# sensors.net
KiCad netlist of a schematic drawn in Altium Designer
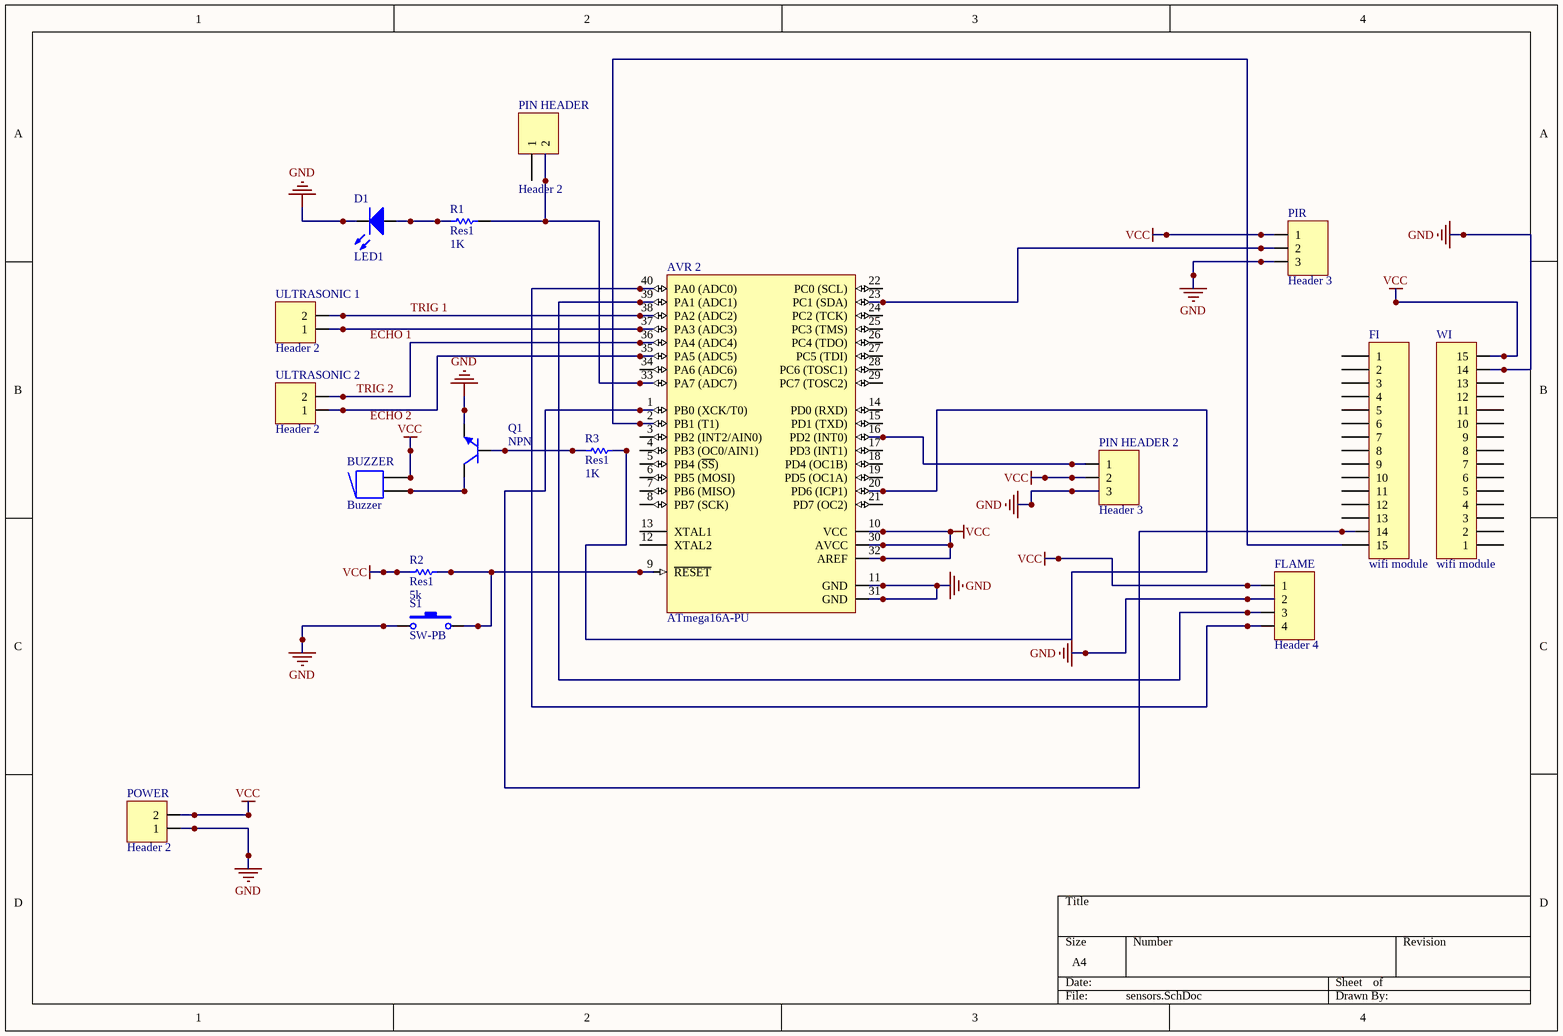
[diagram p0: sensors.SchDoc]

(export (version "E")
  (design (tool "Eeschema 10.0.6"))
  (components
    (comp (ref "AVR 2")
      (value "ATmega16A-PU")
      (footprint "40P6")
      (fields (field (name "PUBLISHER") "Altium Limited"))
      (libsource (lib "Atmel Microcontroller 8-Bit megaAVR") (part "ATmega16A-PU"))
    )
    (comp (ref "BUZZER")
      (value "Buzzer")
      (footprint "ABSM-1574")
      (description "Magnetic Transducer Buzzer")
      (fields (field (name "PUBLISHER") "Altium Limited"))
      (libsource (lib "Miscellaneous Devices") (part "Buzzer"))
    )
    (comp (ref "D1")
      (value "LED1")
      (footprint "LED-1")
      (description "Typical RED GaAs LED")
      (fields (field (name "PUBLISHER") "Altium Limited"))
      (libsource (lib "Miscellaneous Devices") (part "LED1"))
    )
    (comp (ref "FI")
      (value "wifi module")
      (footprint "HDR1X15")
      (description "Header, 15-Pin")
      (fields (field (name "PUBLISHER") "Altium Limited"))
      (libsource (lib "") (part "Header 15_1"))
    )
    (comp (ref "FLAME")
      (value "Header 4")
      (footprint "HDR1X4")
      (description "Header, 4-Pin")
      (fields (field (name "PUBLISHER") "Altium Limited"))
      (libsource (lib "Miscellaneous Connectors") (part "Header 4"))
    )
    (comp (ref "PIN HEADER")
      (value "Header 2")
      (footprint "HDR1X2")
      (description "Header, 2-Pin")
      (fields (field (name "PUBLISHER") "Altium Limited"))
      (libsource (lib "") (part "Header 2_1"))
    )
    (comp (ref "PIN HEADER 2")
      (value "Header 3")
      (footprint "HDR1X3")
      (description "Header, 3-Pin")
      (fields (field (name "PUBLISHER") "Altium Limited"))
      (libsource (lib "Miscellaneous Connectors") (part "Header 3"))
    )
    (comp (ref "PIR")
      (value "Header 3")
      (footprint "HDR1X3")
      (description "Header, 3-Pin")
      (fields (field (name "PUBLISHER") "Altium Limited"))
      (libsource (lib "Miscellaneous Connectors") (part "Header 3"))
    )
    (comp (ref "POWER")
      (value "Header 2")
      (footprint "HDR1X2")
      (description "Header, 2-Pin")
      (fields (field (name "PUBLISHER") "Altium Limited"))
      (libsource (lib "Miscellaneous Connectors") (part "Header 2"))
    )
    (comp (ref "Q1")
      (value "NPN")
      (footprint "TO-226-AA")
      (description "NPN Bipolar Transistor")
      (fields (field (name "PUBLISHER") "Altium Limited"))
      (libsource (lib "Miscellaneous Devices") (part "NPN"))
    )
    (comp (ref "R1")
      (value "Res1")
      (footprint "AXIAL-0.3")
      (description "Resistor")
      (fields (field (name "ALTIUM_VALUE") "1K") (field (name "PUBLISHER") "Altium Limited"))
      (libsource (lib "Miscellaneous Devices") (part "Res1"))
    )
    (comp (ref "R2")
      (value "Res1")
      (footprint "AXIAL-0.3")
      (description "Resistor")
      (fields (field (name "ALTIUM_VALUE") "5k") (field (name "PUBLISHER") "Altium Limited"))
      (libsource (lib "Miscellaneous Devices") (part "Res1"))
    )
    (comp (ref "R3")
      (value "Res1")
      (footprint "AXIAL-0.3")
      (description "Resistor")
      (fields (field (name "ALTIUM_VALUE") "1K") (field (name "PUBLISHER") "Altium Limited"))
      (libsource (lib "Miscellaneous Devices") (part "Res1"))
    )
    (comp (ref "S1")
      (value "SW-PB")
      (footprint "SPST-2")
      (description "Switch")
      (fields (field (name "PUBLISHER") "Altium Limited"))
      (libsource (lib "Miscellaneous Devices") (part "SW-PB"))
    )
    (comp (ref "ULTRASONIC 1")
      (value "Header 2")
      (footprint "HDR1X2")
      (description "Header, 2-Pin")
      (fields (field (name "PUBLISHER") "Altium Limited"))
      (libsource (lib "Miscellaneous Connectors") (part "Header 2"))
    )
    (comp (ref "ULTRASONIC 2")
      (value "Header 2")
      (footprint "HDR1X2")
      (description "Header, 2-Pin")
      (fields (field (name "PUBLISHER") "Altium Limited"))
      (libsource (lib "Miscellaneous Connectors") (part "Header 2"))
    )
    (comp (ref "WI")
      (value "wifi module")
      (footprint "HDR1X15")
      (description "Header, 15-Pin")
      (fields (field (name "PUBLISHER") "Altium Limited"))
      (libsource (lib "Miscellaneous Connectors") (part "Header 15"))
    )
  )
  (nets
    (net (code "3") (name "/TRIG 1") (class "Default")
      (node (ref "AVR 2") (pin "38") (pinfunction "PA2_(ADC2)_38") (pintype "bidirectional"))
      (node (ref "ULTRASONIC 1") (pin "2") (pinfunction "2_2") (pintype "passive"))
    )
    (net (code "4") (name "/TRIG 2") (class "Default")
      (node (ref "AVR 2") (pin "36") (pinfunction "PA4_(ADC4)_36") (pintype "bidirectional"))
      (node (ref "ULTRASONIC 2") (pin "2") (pinfunction "2_2") (pintype "passive"))
    )
    (net (code "5") (name "GND") (class "Default")
      (node (ref "AVR 2") (pin "11") (pinfunction "GND_11") (pintype "power_in"))
      (node (ref "AVR 2") (pin "31") (pinfunction "GND_31") (pintype "power_in"))
      (node (ref "D1") (pin "2") (pinfunction "K_2") (pintype "passive"))
      (node (ref "FLAME") (pin "2") (pinfunction "2_2") (pintype "passive"))
      (node (ref "PIN HEADER 2") (pin "3") (pinfunction "3_3") (pintype "passive"))
      (node (ref "PIR") (pin "3") (pinfunction "3_3") (pintype "passive"))
      (node (ref "POWER") (pin "1") (pinfunction "1_1") (pintype "passive"))
      (node (ref "Q1") (pin "3") (pinfunction "E_3") (pintype "passive"))
      (node (ref "S1") (pin "1") (pinfunction "1_1") (pintype "passive"))
      (node (ref "WI") (pin "14") (pinfunction "14_14") (pintype "passive"))
    )
    (net (code "6") (name "Net-(AVR 2-PA0_(ADC0))") (class "Default")
      (node (ref "AVR 2") (pin "40") (pinfunction "PA0_(ADC0)_40") (pintype "bidirectional"))
      (node (ref "FLAME") (pin "4") (pinfunction "4_4") (pintype "passive"))
    )
    (net (code "7") (name "Net-(AVR 2-PA1_(ADC1))") (class "Default")
      (node (ref "AVR 2") (pin "39") (pinfunction "PA1_(ADC1)_39") (pintype "bidirectional"))
      (node (ref "FLAME") (pin "3") (pinfunction "3_3") (pintype "passive"))
    )
    (net (code "8") (name "Net-(AVR 2-PA3_(ADC3))") (class "Default")
      (node (ref "AVR 2") (pin "37") (pinfunction "PA3_(ADC3)_37") (pintype "bidirectional"))
      (node (ref "ULTRASONIC 1") (pin "1") (pinfunction "1_1") (pintype "passive"))
    )
    (net (code "9") (name "Net-(AVR 2-PA5_(ADC5))") (class "Default")
      (node (ref "AVR 2") (pin "35") (pinfunction "PA5_(ADC5)_35") (pintype "bidirectional"))
      (node (ref "ULTRASONIC 2") (pin "1") (pinfunction "1_1") (pintype "passive"))
    )
    (net (code "10") (name "Net-(AVR 2-PA7_(ADC7))") (class "Default")
      (node (ref "AVR 2") (pin "33") (pinfunction "PA7_(ADC7)_33") (pintype "bidirectional"))
      (node (ref "PIN HEADER") (pin "2") (pinfunction "2_2") (pintype "passive"))
      (node (ref "R1") (pin "1") (pinfunction "1_1") (pintype "passive"))
    )
    (net (code "11") (name "Net-(AVR 2-PB0_(XCK{slash}T0))") (class "Default")
      (node (ref "AVR 2") (pin "1") (pinfunction "PB0_(XCK/T0)_1") (pintype "bidirectional"))
      (node (ref "FI") (pin "14") (pinfunction "14_14") (pintype "passive"))
    )
    (net (code "12") (name "Net-(AVR 2-PB1_(T1))") (class "Default")
      (node (ref "AVR 2") (pin "2") (pinfunction "PB1_(T1)_2") (pintype "bidirectional"))
      (node (ref "FI") (pin "15") (pinfunction "15_15") (pintype "passive"))
    )
    (net (code "13") (name "Net-(AVR 2-PC1_(SDA))") (class "Default")
      (node (ref "AVR 2") (pin "23") (pinfunction "PC1_(SDA)_23") (pintype "bidirectional"))
      (node (ref "PIR") (pin "2") (pinfunction "2_2") (pintype "passive"))
    )
    (net (code "14") (name "Net-(AVR 2-PD2_(INT0))") (class "Default")
      (node (ref "AVR 2") (pin "16") (pinfunction "PD2_(INT0)_16") (pintype "bidirectional"))
      (node (ref "PIN HEADER 2") (pin "1") (pinfunction "1_1") (pintype "passive"))
    )
    (net (code "15") (name "Net-(AVR 2-PD6_(ICP1))") (class "Default")
      (node (ref "AVR 2") (pin "20") (pinfunction "PD6_(ICP1)_20") (pintype "bidirectional"))
      (node (ref "R3") (pin "2") (pinfunction "2_2") (pintype "passive"))
    )
    (net (code "16") (name "Net-(AVR 2-~{RESET})") (class "Default")
      (node (ref "AVR 2") (pin "9") (pinfunction "~{RESET}_9") (pintype "input"))
      (node (ref "R2") (pin "1") (pinfunction "1_1") (pintype "passive"))
      (node (ref "S1") (pin "2") (pinfunction "2_2") (pintype "passive"))
    )
    (net (code "17") (name "Net-(D1-A)") (class "Default")
      (node (ref "D1") (pin "1") (pinfunction "A_1") (pintype "passive"))
      (node (ref "R1") (pin "2") (pinfunction "2_2") (pintype "passive"))
    )
    (net (code "18") (name "Net-(Q1-B)") (class "Default")
      (node (ref "Q1") (pin "2") (pinfunction "B_2") (pintype "passive"))
      (node (ref "R3") (pin "1") (pinfunction "1_1") (pintype "passive"))
    )
    (net (code "19") (name "Net-(Q1-C)") (class "Default")
      (node (ref "BUZZER") (pin "1") (pinfunction "1_1") (pintype "passive"))
      (node (ref "BUZZER") (pin "1A") (pinfunction "1A_1A") (pintype "passive"))
      (node (ref "Q1") (pin "1") (pinfunction "C_1") (pintype "passive"))
    )
    (net (code "20") (name "VCC") (class "Default")
      (node (ref "AVR 2") (pin "10") (pinfunction "VCC_10") (pintype "power_in"))
      (node (ref "AVR 2") (pin "30") (pinfunction "AVCC_30") (pintype "power_in"))
      (node (ref "AVR 2") (pin "32") (pinfunction "AREF_32") (pintype "power_in"))
      (node (ref "BUZZER") (pin "2") (pinfunction "2_2") (pintype "passive"))
      (node (ref "BUZZER") (pin "2A") (pinfunction "2A_2A") (pintype "passive"))
      (node (ref "FLAME") (pin "1") (pinfunction "1_1") (pintype "passive"))
      (node (ref "PIN HEADER 2") (pin "2") (pinfunction "2_2") (pintype "passive"))
      (node (ref "PIR") (pin "1") (pinfunction "1_1") (pintype "passive"))
      (node (ref "POWER") (pin "2") (pinfunction "2_2") (pintype "passive"))
      (node (ref "R2") (pin "2") (pinfunction "2_2") (pintype "passive"))
      (node (ref "WI") (pin "15") (pinfunction "15_15") (pintype "passive"))
    )
    (net (code "21") (name "unconnected-(AVR 2-PA6_(ADC6)-Pad34)") (class "Default")
      (node (ref "AVR 2") (pin "34") (pinfunction "PA6_(ADC6)_34") (pintype "bidirectional"))
    )
    (net (code "22") (name "unconnected-(AVR 2-PB2_(INT2{slash}AIN0)-Pad3)") (class "Default")
      (node (ref "AVR 2") (pin "3") (pinfunction "PB2_(INT2/AIN0)_3") (pintype "bidirectional"))
    )
    (net (code "23") (name "unconnected-(AVR 2-PB3_(OC0{slash}AIN1)-Pad4)") (class "Default")
      (node (ref "AVR 2") (pin "4") (pinfunction "PB3_(OC0/AIN1)_4") (pintype "bidirectional"))
    )
    (net (code "24") (name "unconnected-(AVR 2-PB4_(~{SS})-Pad5)") (class "Default")
      (node (ref "AVR 2") (pin "5") (pinfunction "PB4_(~{SS})_5") (pintype "bidirectional"))
    )
    (net (code "25") (name "unconnected-(AVR 2-PB5_(MOSI)-Pad6)") (class "Default")
      (node (ref "AVR 2") (pin "6") (pinfunction "PB5_(MOSI)_6") (pintype "bidirectional"))
    )
    (net (code "26") (name "unconnected-(AVR 2-PB6_(MISO)-Pad7)") (class "Default")
      (node (ref "AVR 2") (pin "7") (pinfunction "PB6_(MISO)_7") (pintype "bidirectional"))
    )
    (net (code "27") (name "unconnected-(AVR 2-PB7_(SCK)-Pad8)") (class "Default")
      (node (ref "AVR 2") (pin "8") (pinfunction "PB7_(SCK)_8") (pintype "bidirectional"))
    )
    (net (code "28") (name "unconnected-(AVR 2-PC0_(SCL)-Pad22)") (class "Default")
      (node (ref "AVR 2") (pin "22") (pinfunction "PC0_(SCL)_22") (pintype "bidirectional"))
    )
    (net (code "29") (name "unconnected-(AVR 2-PC2_(TCK)-Pad24)") (class "Default")
      (node (ref "AVR 2") (pin "24") (pinfunction "PC2_(TCK)_24") (pintype "bidirectional"))
    )
    (net (code "30") (name "unconnected-(AVR 2-PC3_(TMS)-Pad25)") (class "Default")
      (node (ref "AVR 2") (pin "25") (pinfunction "PC3_(TMS)_25") (pintype "bidirectional"))
    )
    (net (code "31") (name "unconnected-(AVR 2-PC4_(TDO)-Pad26)") (class "Default")
      (node (ref "AVR 2") (pin "26") (pinfunction "PC4_(TDO)_26") (pintype "bidirectional"))
    )
    (net (code "32") (name "unconnected-(AVR 2-PC5_(TDI)-Pad27)") (class "Default")
      (node (ref "AVR 2") (pin "27") (pinfunction "PC5_(TDI)_27") (pintype "bidirectional"))
    )
    (net (code "33") (name "unconnected-(AVR 2-PC6_(TOSC1)-Pad28)") (class "Default")
      (node (ref "AVR 2") (pin "28") (pinfunction "PC6_(TOSC1)_28") (pintype "bidirectional"))
    )
    (net (code "34") (name "unconnected-(AVR 2-PC7_(TOSC2)-Pad29)") (class "Default")
      (node (ref "AVR 2") (pin "29") (pinfunction "PC7_(TOSC2)_29") (pintype "bidirectional"))
    )
    (net (code "35") (name "unconnected-(AVR 2-PD0_(RXD)-Pad14)") (class "Default")
      (node (ref "AVR 2") (pin "14") (pinfunction "PD0_(RXD)_14") (pintype "bidirectional"))
    )
    (net (code "36") (name "unconnected-(AVR 2-PD1_(TXD)-Pad15)") (class "Default")
      (node (ref "AVR 2") (pin "15") (pinfunction "PD1_(TXD)_15") (pintype "bidirectional"))
    )
    (net (code "37") (name "unconnected-(AVR 2-PD3_(INT1)-Pad17)") (class "Default")
      (node (ref "AVR 2") (pin "17") (pinfunction "PD3_(INT1)_17") (pintype "bidirectional"))
    )
    (net (code "38") (name "unconnected-(AVR 2-PD4_(OC1B)-Pad18)") (class "Default")
      (node (ref "AVR 2") (pin "18") (pinfunction "PD4_(OC1B)_18") (pintype "bidirectional"))
    )
    (net (code "39") (name "unconnected-(AVR 2-PD5_(OC1A)-Pad19)") (class "Default")
      (node (ref "AVR 2") (pin "19") (pinfunction "PD5_(OC1A)_19") (pintype "bidirectional"))
    )
    (net (code "40") (name "unconnected-(AVR 2-PD7_(OC2)-Pad21)") (class "Default")
      (node (ref "AVR 2") (pin "21") (pinfunction "PD7_(OC2)_21") (pintype "bidirectional"))
    )
    (net (code "41") (name "unconnected-(AVR 2-XTAL1-Pad13)") (class "Default")
      (node (ref "AVR 2") (pin "13") (pinfunction "XTAL1_13") (pintype "passive"))
    )
    (net (code "42") (name "unconnected-(AVR 2-XTAL2-Pad12)") (class "Default")
      (node (ref "AVR 2") (pin "12") (pinfunction "XTAL2_12") (pintype "passive"))
    )
    (net (code "43") (name "unconnected-(FI-Pad1)") (class "Default")
      (node (ref "FI") (pin "1") (pinfunction "1_1") (pintype "passive"))
    )
    (net (code "44") (name "unconnected-(FI-Pad2)") (class "Default")
      (node (ref "FI") (pin "2") (pinfunction "2_2") (pintype "passive"))
    )
    (net (code "45") (name "unconnected-(FI-Pad3)") (class "Default")
      (node (ref "FI") (pin "3") (pinfunction "3_3") (pintype "passive"))
    )
    (net (code "46") (name "unconnected-(FI-Pad4)") (class "Default")
      (node (ref "FI") (pin "4") (pinfunction "4_4") (pintype "passive"))
    )
    (net (code "47") (name "unconnected-(FI-Pad5)") (class "Default")
      (node (ref "FI") (pin "5") (pinfunction "5_5") (pintype "passive"))
    )
    (net (code "48") (name "unconnected-(FI-Pad6)") (class "Default")
      (node (ref "FI") (pin "6") (pinfunction "6_6") (pintype "passive"))
    )
    (net (code "49") (name "unconnected-(FI-Pad7)") (class "Default")
      (node (ref "FI") (pin "7") (pinfunction "7_7") (pintype "passive"))
    )
    (net (code "50") (name "unconnected-(FI-Pad8)") (class "Default")
      (node (ref "FI") (pin "8") (pinfunction "8_8") (pintype "passive"))
    )
    (net (code "51") (name "unconnected-(FI-Pad9)") (class "Default")
      (node (ref "FI") (pin "9") (pinfunction "9_9") (pintype "passive"))
    )
    (net (code "52") (name "unconnected-(FI-Pad10)") (class "Default")
      (node (ref "FI") (pin "10") (pinfunction "10_10") (pintype "passive"))
    )
    (net (code "53") (name "unconnected-(FI-Pad11)") (class "Default")
      (node (ref "FI") (pin "11") (pinfunction "11_11") (pintype "passive"))
    )
    (net (code "54") (name "unconnected-(FI-Pad12)") (class "Default")
      (node (ref "FI") (pin "12") (pinfunction "12_12") (pintype "passive"))
    )
    (net (code "55") (name "unconnected-(FI-Pad13)") (class "Default")
      (node (ref "FI") (pin "13") (pinfunction "13_13") (pintype "passive"))
    )
    (net (code "56") (name "unconnected-(PIN HEADER-Pad1)") (class "Default")
      (node (ref "PIN HEADER") (pin "1") (pinfunction "1_1") (pintype "passive"))
    )
    (net (code "57") (name "unconnected-(WI-Pad1)") (class "Default")
      (node (ref "WI") (pin "1") (pinfunction "1_1") (pintype "passive"))
    )
    (net (code "58") (name "unconnected-(WI-Pad2)") (class "Default")
      (node (ref "WI") (pin "2") (pinfunction "2_2") (pintype "passive"))
    )
    (net (code "59") (name "unconnected-(WI-Pad3)") (class "Default")
      (node (ref "WI") (pin "3") (pinfunction "3_3") (pintype "passive"))
    )
    (net (code "60") (name "unconnected-(WI-Pad4)") (class "Default")
      (node (ref "WI") (pin "4") (pinfunction "4_4") (pintype "passive"))
    )
    (net (code "61") (name "unconnected-(WI-Pad5)") (class "Default")
      (node (ref "WI") (pin "5") (pinfunction "5_5") (pintype "passive"))
    )
    (net (code "62") (name "unconnected-(WI-Pad6)") (class "Default")
      (node (ref "WI") (pin "6") (pinfunction "6_6") (pintype "passive"))
    )
    (net (code "63") (name "unconnected-(WI-Pad7)") (class "Default")
      (node (ref "WI") (pin "7") (pinfunction "7_7") (pintype "passive"))
    )
    (net (code "64") (name "unconnected-(WI-Pad8)") (class "Default")
      (node (ref "WI") (pin "8") (pinfunction "8_8") (pintype "passive"))
    )
    (net (code "65") (name "unconnected-(WI-Pad9)") (class "Default")
      (node (ref "WI") (pin "9") (pinfunction "9_9") (pintype "passive"))
    )
    (net (code "66") (name "unconnected-(WI-Pad10)") (class "Default")
      (node (ref "WI") (pin "10") (pinfunction "10_10") (pintype "passive"))
    )
    (net (code "67") (name "unconnected-(WI-Pad11)") (class "Default")
      (node (ref "WI") (pin "11") (pinfunction "11_11") (pintype "passive"))
    )
    (net (code "68") (name "unconnected-(WI-Pad12)") (class "Default")
      (node (ref "WI") (pin "12") (pinfunction "12_12") (pintype "passive"))
    )
    (net (code "69") (name "unconnected-(WI-Pad13)") (class "Default")
      (node (ref "WI") (pin "13") (pinfunction "13_13") (pintype "passive"))
    )
  )
)
